# SCH_voltage-multiplier_2026-06-30.net
KiCad netlist of a schematic drawn in EasyEDA
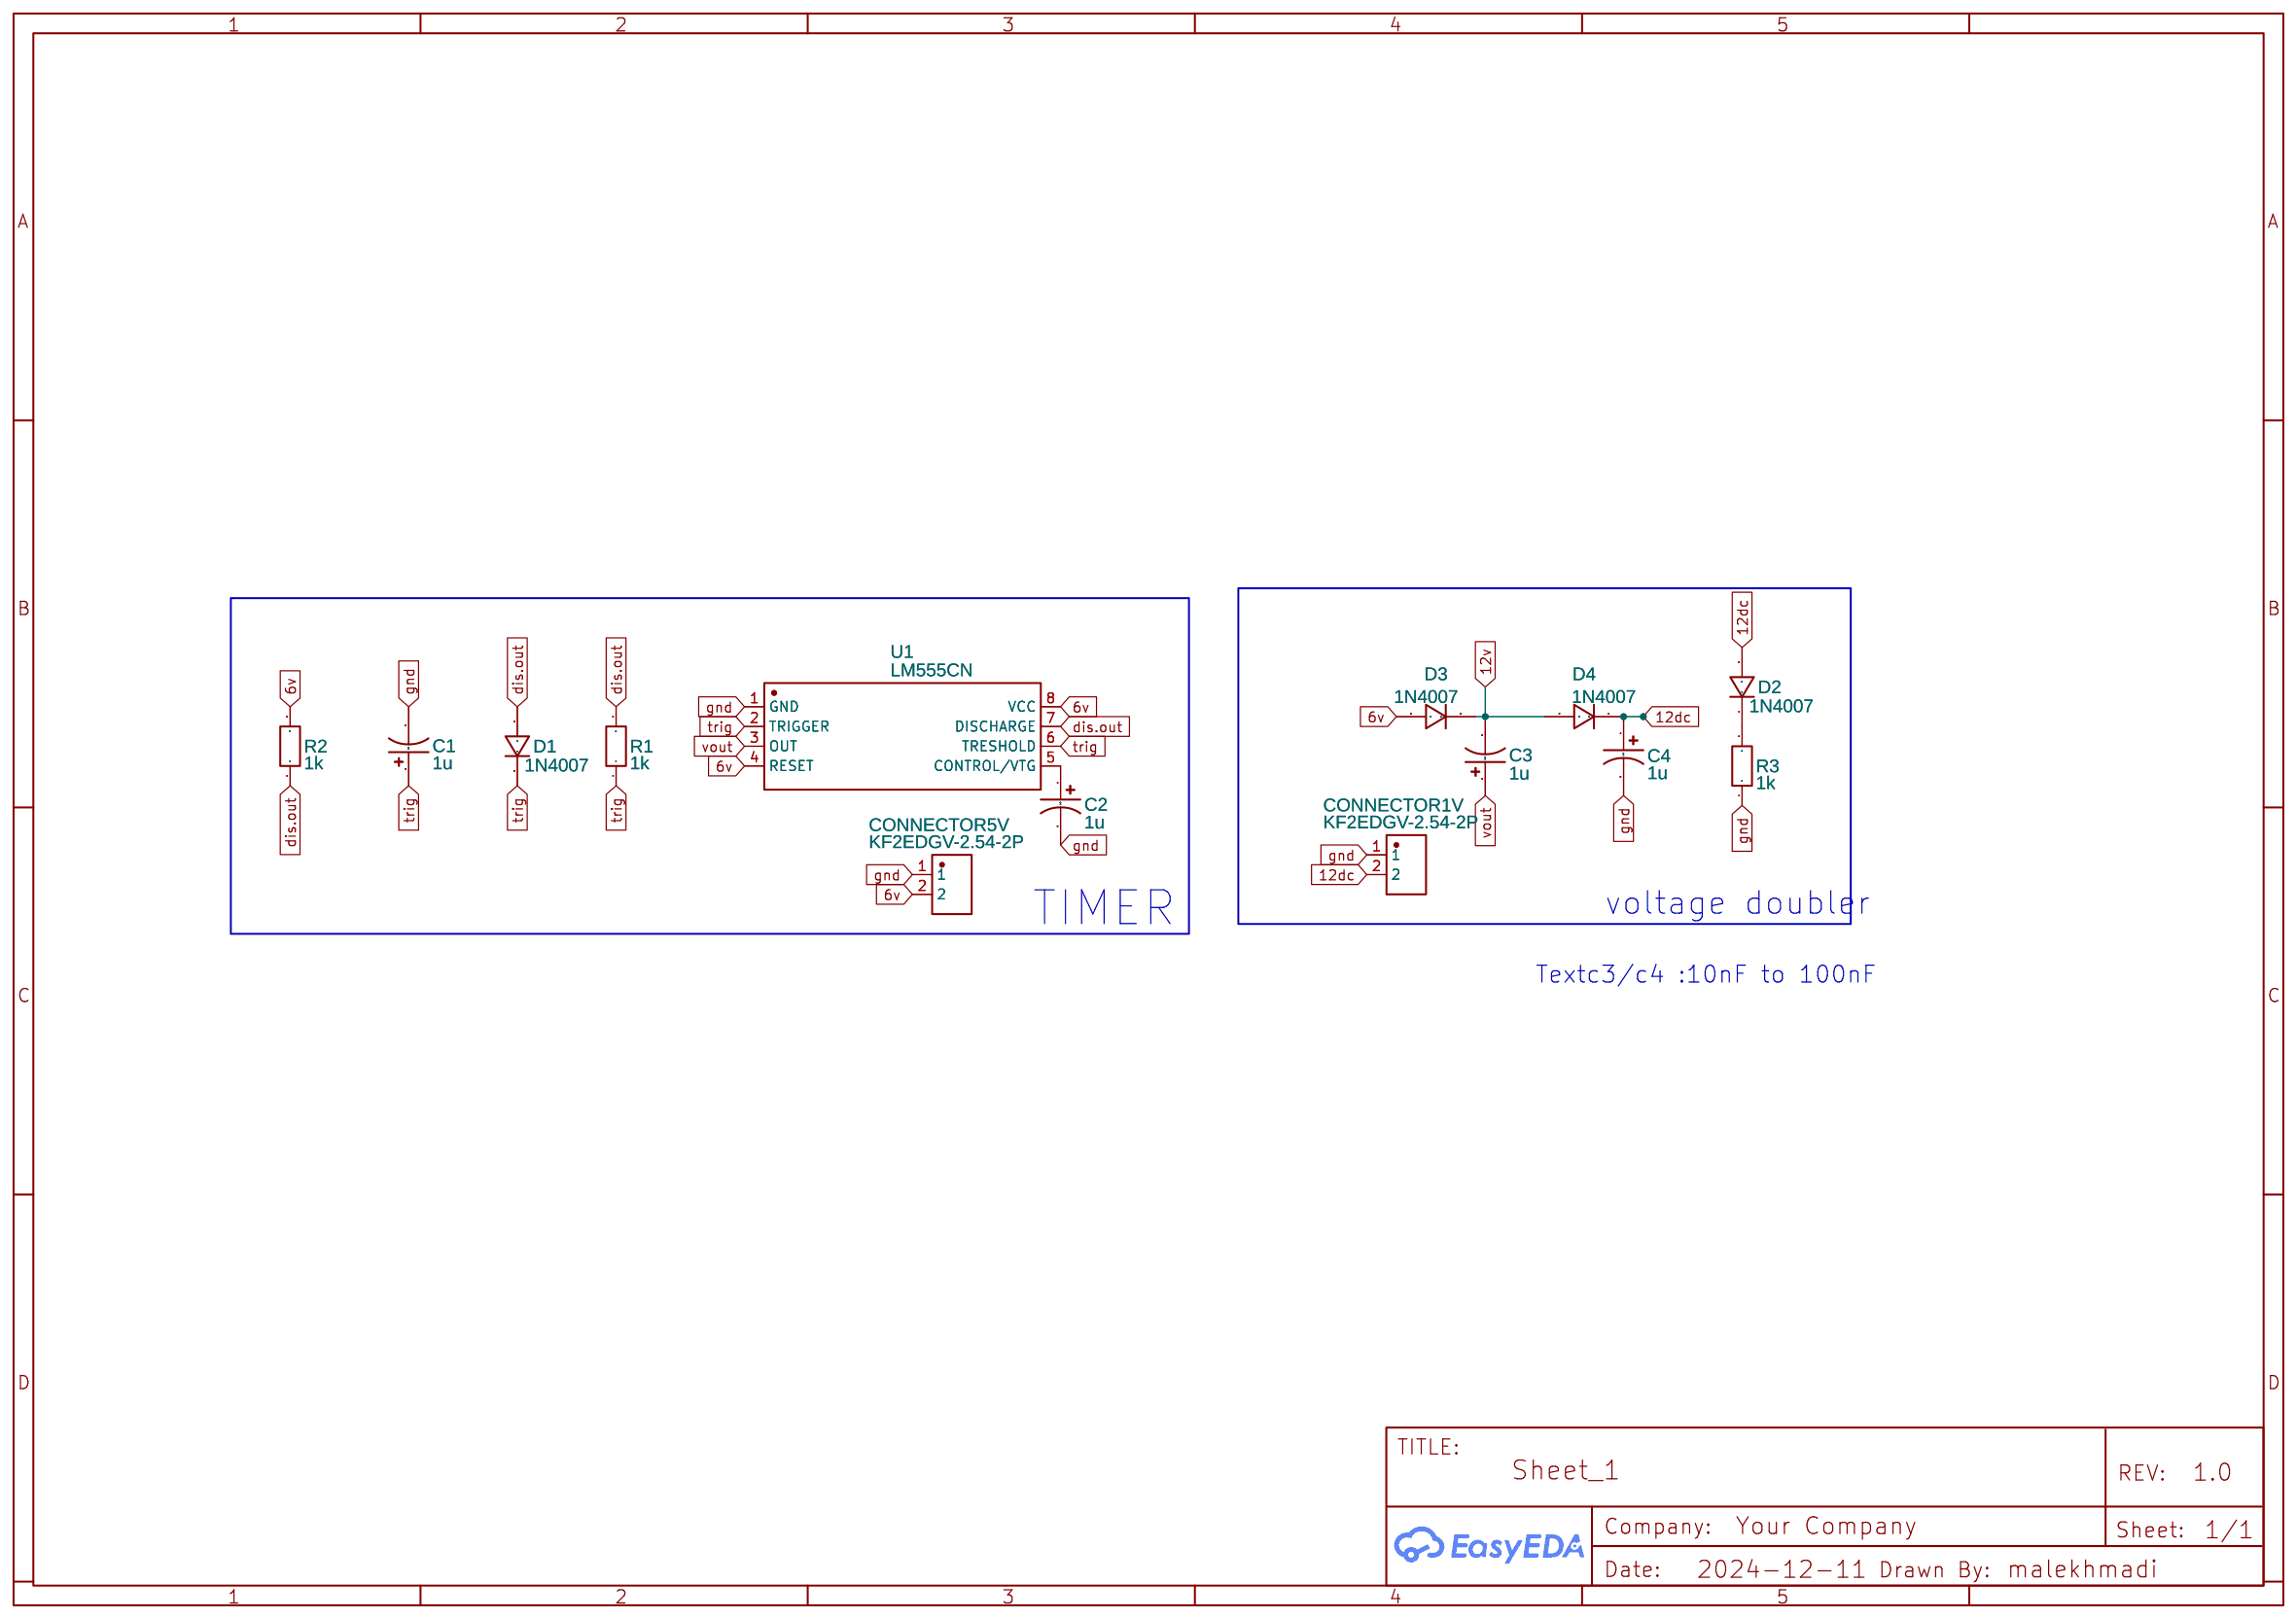
[diagram p0: schematic sheet]

(export (version "E")
  (design (tool "Eeschema 10.0.6"))
  (components
    (comp (ref "C1") (value "1u") (libsource (lib "") (part "CE_TH_D4.0×F1.5_US_1")))
    (comp (ref "C2") (value "1u") (libsource (lib "") (part "CE_TH_D4.0×F1.5_US")))
    (comp (ref "C3") (value "1u") (libsource (lib "") (part "CE_TH_D4.0×F1.5_US_2")))
    (comp (ref "C4") (value "1u") (libsource (lib "") (part "CE_TH_D4.0×F1.5_US")))
    (comp (ref "CONNECTOR1V")
      (value "KF2EDGV-2.54-2P")
      (fields (field (name "Manufacturer") "KEFA(科发)"))
      (libsource (lib "") (part "KF2EDGV-2.54-2P_1"))
    )
    (comp (ref "CONNECTOR5V")
      (value "KF2EDGV-2.54-2P")
      (fields (field (name "Manufacturer") "KEFA(科发)"))
      (libsource (lib "") (part "KF2EDGV-2.54-2P"))
    )
    (comp (ref "D1")
      (value "1N4007")
      (fields (field (name "Manufacturer") "SEMTECH"))
      (libsource (lib "") (part "1N4007_1"))
    )
    (comp (ref "D2")
      (value "1N4007")
      (fields (field (name "Manufacturer") "SEMTECH"))
      (libsource (lib "") (part "1N4007_1"))
    )
    (comp (ref "D3")
      (value "1N4007")
      (fields (field (name "Manufacturer") "SEMTECH"))
      (libsource (lib "") (part "1N4007"))
    )
    (comp (ref "D4")
      (value "1N4007")
      (fields (field (name "Manufacturer") "SEMTECH"))
      (libsource (lib "") (part "1N4007"))
    )
    (comp (ref "R1") (value "1k") (libsource (lib "") (part "R_AXIAL-0.3_EU")))
    (comp (ref "R2") (value "1k") (libsource (lib "") (part "R_AXIAL-0.3_EU")))
    (comp (ref "R3") (value "1k") (libsource (lib "") (part "R_AXIAL-0.3_EU")))
    (comp (ref "U1")
      (value "LM555CN")
      (fields (field (name "Manufacturer") "onsemi(安森美)"))
      (libsource (lib "") (part "LM555CN"))
    )
  )
  (nets
    (net (code "1") (name "6v") (class "Default")
      (node (ref "CONNECTOR5V") (pin "2") (pinfunction "2_2") (pintype "unspecified"))
      (node (ref "D3") (pin "2") (pinfunction "2_2") (pintype "unspecified"))
      (node (ref "R2") (pin "2") (pinfunction "2_2") (pintype "unspecified"))
      (node (ref "U1") (pin "4") (pinfunction "RESET_4") (pintype "unspecified"))
      (node (ref "U1") (pin "8") (pinfunction "VCC_8") (pintype "unspecified"))
    )
    (net (code "2") (name "12dc") (class "Default")
      (node (ref "C4") (pin "1") (pinfunction "1_1") (pintype "unspecified"))
      (node (ref "CONNECTOR1V") (pin "2") (pinfunction "2_2") (pintype "unspecified"))
      (node (ref "D2") (pin "2") (pinfunction "2_2") (pintype "unspecified"))
      (node (ref "D4") (pin "1") (pinfunction "1_1") (pintype "unspecified"))
    )
    (net (code "3") (name "12v") (class "Default")
      (node (ref "C3") (pin "2") (pinfunction "2_2") (pintype "unspecified"))
      (node (ref "D3") (pin "1") (pinfunction "1_1") (pintype "unspecified"))
      (node (ref "D4") (pin "2") (pinfunction "2_2") (pintype "unspecified"))
    )
    (net (code "4") (name "Net-(D2-Pad1)") (class "Default")
      (node (ref "D2") (pin "1") (pinfunction "1_1") (pintype "unspecified"))
      (node (ref "R3") (pin "2") (pinfunction "2_2") (pintype "unspecified"))
    )
    (net (code "5") (name "Net-(U1-CONTROL{slash}VTG)") (class "Default")
      (node (ref "C2") (pin "1") (pinfunction "1_1") (pintype "unspecified"))
      (node (ref "U1") (pin "5") (pinfunction "CONTROL/VTG_5") (pintype "unspecified"))
    )
    (net (code "6") (name "dis.out") (class "Default")
      (node (ref "D1") (pin "2") (pinfunction "2_2") (pintype "unspecified"))
      (node (ref "R1") (pin "2") (pinfunction "2_2") (pintype "unspecified"))
      (node (ref "R2") (pin "1") (pinfunction "1_1") (pintype "unspecified"))
      (node (ref "U1") (pin "7") (pinfunction "DISCHARGE_7") (pintype "unspecified"))
    )
    (net (code "7") (name "gnd") (class "Default")
      (node (ref "C1") (pin "2") (pinfunction "2_2") (pintype "unspecified"))
      (node (ref "C2") (pin "2") (pinfunction "2_2") (pintype "unspecified"))
      (node (ref "C4") (pin "2") (pinfunction "2_2") (pintype "unspecified"))
      (node (ref "CONNECTOR1V") (pin "1") (pinfunction "1_1") (pintype "unspecified"))
      (node (ref "CONNECTOR5V") (pin "1") (pinfunction "1_1") (pintype "unspecified"))
      (node (ref "R3") (pin "1") (pinfunction "1_1") (pintype "unspecified"))
      (node (ref "U1") (pin "1") (pinfunction "GND_1") (pintype "unspecified"))
    )
    (net (code "8") (name "trig") (class "Default")
      (node (ref "C1") (pin "1") (pinfunction "1_1") (pintype "unspecified"))
      (node (ref "D1") (pin "1") (pinfunction "1_1") (pintype "unspecified"))
      (node (ref "R1") (pin "1") (pinfunction "1_1") (pintype "unspecified"))
      (node (ref "U1") (pin "2") (pinfunction "TRIGGER_2") (pintype "unspecified"))
      (node (ref "U1") (pin "6") (pinfunction "TRESHOLD_6") (pintype "unspecified"))
    )
    (net (code "9") (name "vout") (class "Default")
      (node (ref "C3") (pin "1") (pinfunction "1_1") (pintype "unspecified"))
      (node (ref "U1") (pin "3") (pinfunction "OUT_3") (pintype "unspecified"))
    )
  )
)
